# 780-00012-P1_Sch_M2_Focus_Drive_old.net
KiCad netlist of a schematic drawn in Altium Designer
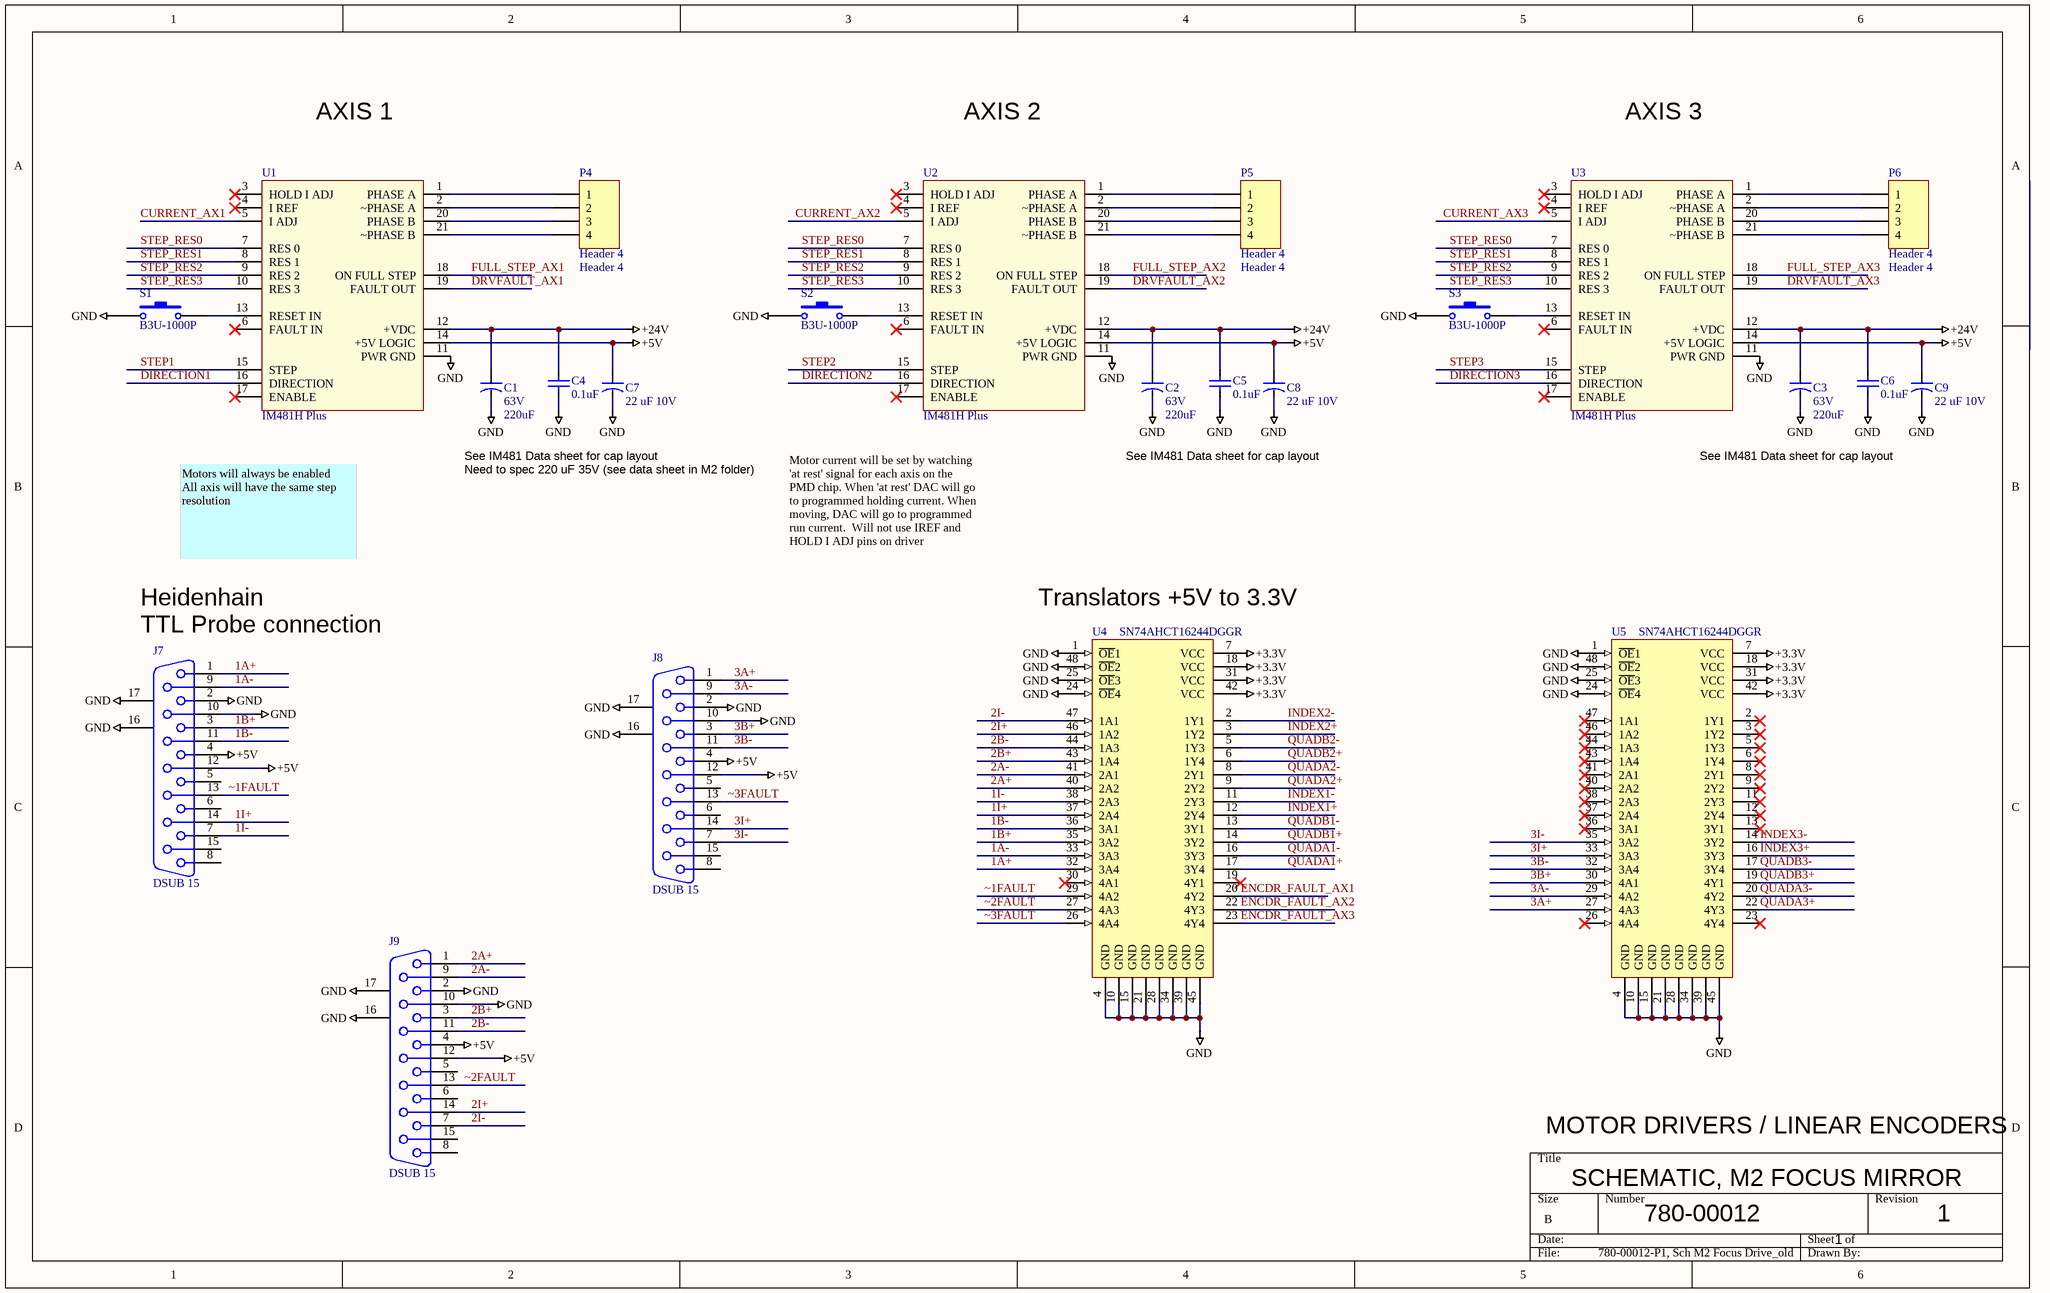
[diagram p0: 780-00012-P1, Sch M2 Focus Drive_old.SchDoc]

(export (version "E")
  (design (tool "Eeschema 10.0.6"))
  (components
    (comp (ref "C1")
      (value "63V")
      (footprint "CAP 220uF 63V")
      (description "CAP 220UF 63V ELECT MVH SMD")
      (fields (field (name "MANUFACTURER") "United Chemi-Con") (field (name "ALTIUM_VALUE") "220uF"))
      (libsource (lib "Richs Schematic Components") (part "Cap 220uF, 63V"))
    )
    (comp (ref "C2")
      (value "63V")
      (footprint "CAP 220uF 63V")
      (description "CAP 220UF 63V ELECT MVH SMD")
      (fields (field (name "MANUFACTURER") "United Chemi-Con") (field (name "ALTIUM_VALUE") "220uF"))
      (libsource (lib "Richs Schematic Components") (part "Cap 220uF, 63V"))
    )
    (comp (ref "C3")
      (value "63V")
      (footprint "CAP 220uF 63V")
      (description "CAP 220UF 63V ELECT MVH SMD")
      (fields (field (name "MANUFACTURER") "United Chemi-Con") (field (name "ALTIUM_VALUE") "220uF"))
      (libsource (lib "Richs Schematic Components") (part "Cap 220uF, 63V"))
    )
    (comp (ref "C4")
      (value "0.1uF")
      (footprint "SMD_0805")
      (description "Capacitor")
      (fields (field (name "Comment") "Cap SMD"))
      (libsource (lib "Richs Schematic Components") (part "Cap SMD"))
    )
    (comp (ref "C5")
      (value "0.1uF")
      (footprint "SMD_0805")
      (description "Capacitor")
      (fields (field (name "Comment") "Cap SMD"))
      (libsource (lib "Richs Schematic Components") (part "Cap SMD"))
    )
    (comp (ref "C6")
      (value "0.1uF")
      (footprint "SMD_0805")
      (description "Capacitor")
      (fields (field (name "Comment") "Cap SMD"))
      (libsource (lib "Richs Schematic Components") (part "Cap SMD"))
    )
    (comp (ref "C7")
      (value "22 uF 10V")
      (footprint "SMD_CAP_3216")
      (description "outline 3.2mm x 1.6mm")
      (fields (field (name "MANUFACTURER") "KEMET") (field (name "Comment") "16V"))
      (libsource (lib "Richs Schematic Components") (part "Cap Tant 16V"))
    )
    (comp (ref "C8")
      (value "22 uF 10V")
      (footprint "SMD_CAP_3216")
      (description "outline 3.2mm x 1.6mm")
      (fields (field (name "MANUFACTURER") "KEMET") (field (name "Comment") "16V"))
      (libsource (lib "Richs Schematic Components") (part "Cap Tant 16V"))
    )
    (comp (ref "C9")
      (value "22 uF 10V")
      (footprint "SMD_CAP_3216")
      (description "outline 3.2mm x 1.6mm")
      (fields (field (name "MANUFACTURER") "KEMET") (field (name "Comment") "16V"))
      (libsource (lib "Richs Schematic Components") (part "Cap Tant 16V"))
    )
    (comp (ref "J7")
      (value "DSUB 15")
      (footprint "DSUB15 PCB VERT Female")
      (description "Receptacle Assembly, 15 Position")
      (fields (field (name "PUBLISHER") "Altium Limited"))
      (libsource (lib "Richs Schematic Components") (part "DSUB 15"))
    )
    (comp (ref "J8")
      (value "DSUB 15")
      (footprint "DSUB15 PCB VERT Female")
      (description "Receptacle Assembly, 15 Position")
      (fields (field (name "PUBLISHER") "Altium Limited"))
      (libsource (lib "Richs Schematic Components") (part "DSUB 15"))
    )
    (comp (ref "J9")
      (value "DSUB 15")
      (footprint "DSUB15 PCB VERT Female")
      (description "Receptacle Assembly, 15 Position")
      (fields (field (name "PUBLISHER") "Altium Limited"))
      (libsource (lib "Richs Schematic Components") (part "DSUB 15"))
    )
    (comp (ref "P4")
      (value "Header 4")
      (footprint "HDR1X4 for IDC")
      (description "Header, 4-Pin")
      (fields (field (name "ALTIUM_VALUE") "Header 4"))
      (libsource (lib "Richs Schematic Components") (part "Header 4"))
    )
    (comp (ref "P5")
      (value "Header 4")
      (footprint "HDR1X4 for IDC")
      (description "Header, 4-Pin")
      (fields (field (name "ALTIUM_VALUE") "Header 4"))
      (libsource (lib "Richs Schematic Components") (part "Header 4"))
    )
    (comp (ref "P6")
      (value "Header 4")
      (footprint "HDR1X4 for IDC")
      (description "Header, 4-Pin")
      (fields (field (name "ALTIUM_VALUE") "Header 4"))
      (libsource (lib "Richs Schematic Components") (part "Header 4"))
    )
    (comp (ref "S1")
      (value "B3U-1000P")
      (footprint "B3U-1000P")
      (description "Switch")
      (fields (field (name "MANUFACTURER") "Omron Electronics"))
      (libsource (lib "Miscellaneous Devices") (part "SW-PB"))
    )
    (comp (ref "S2")
      (value "B3U-1000P")
      (footprint "B3U-1000P")
      (description "Switch")
      (fields (field (name "MANUFACTURER") "Omron Electronics"))
      (libsource (lib "Miscellaneous Devices") (part "SW-PB"))
    )
    (comp (ref "S3")
      (value "B3U-1000P")
      (footprint "B3U-1000P")
      (description "Switch")
      (fields (field (name "MANUFACTURER") "Omron Electronics"))
      (libsource (lib "Miscellaneous Devices") (part "SW-PB"))
    )
    (comp (ref "U1")
      (value "IM481H Plus")
      (footprint "IM481H Vertical")
      (description "Hybrid stepper motor driver")
      (libsource (lib "Richs Schematic Components") (part "IM481H Plus"))
    )
    (comp (ref "U2")
      (value "IM481H Plus")
      (footprint "IM481H Vertical")
      (description "Hybrid stepper motor driver")
      (libsource (lib "Richs Schematic Components") (part "IM481H Plus"))
    )
    (comp (ref "U3")
      (value "IM481H Plus")
      (footprint "IM481H Vertical")
      (description "Hybrid stepper motor driver")
      (libsource (lib "Richs Schematic Components") (part "IM481H Plus"))
    )
    (comp (ref "U4")
      (value "SN74AHCT16244DGGR")
      (footprint "DGG048_N")
      (description "16-Bit Buffer/Driver with 3-State Outputs")
      (fields (field (name "PUBLISHER") "Altium Limited"))
      (libsource (lib "TI Logic Buffer Line Driver") (part "SN74AHCT16244DGGR"))
    )
    (comp (ref "U5")
      (value "SN74AHCT16244DGGR")
      (footprint "DGG048_N")
      (description "16-Bit Buffer/Driver with 3-State Outputs")
      (fields (field (name "PUBLISHER") "Altium Limited"))
      (libsource (lib "TI Logic Buffer Line Driver") (part "SN74AHCT16244DGGR"))
    )
  )
  (nets
    (net (code "1") (name "+3.3V") (class "Default")
      (node (ref "U4") (pin "18") (pinfunction "VCC_18") (pintype "power_in"))
      (node (ref "U4") (pin "31") (pinfunction "VCC_31") (pintype "power_in"))
      (node (ref "U4") (pin "42") (pinfunction "VCC_42") (pintype "power_in"))
      (node (ref "U4") (pin "7") (pinfunction "VCC_7") (pintype "power_in"))
      (node (ref "U5") (pin "18") (pinfunction "VCC_18") (pintype "power_in"))
      (node (ref "U5") (pin "31") (pinfunction "VCC_31") (pintype "power_in"))
      (node (ref "U5") (pin "42") (pinfunction "VCC_42") (pintype "power_in"))
      (node (ref "U5") (pin "7") (pinfunction "VCC_7") (pintype "power_in"))
    )
    (net (code "2") (name "+5V") (class "Default")
      (node (ref "C7") (pin "1") (pinfunction "1_1") (pintype "passive"))
      (node (ref "C8") (pin "1") (pinfunction "1_1") (pintype "passive"))
      (node (ref "C9") (pin "1") (pinfunction "1_1") (pintype "passive"))
      (node (ref "J7") (pin "12") (pinfunction "12_12") (pintype "passive"))
      (node (ref "J7") (pin "4") (pinfunction "4_4") (pintype "passive"))
      (node (ref "J8") (pin "12") (pinfunction "12_12") (pintype "passive"))
      (node (ref "J8") (pin "4") (pinfunction "4_4") (pintype "passive"))
      (node (ref "J9") (pin "12") (pinfunction "12_12") (pintype "passive"))
      (node (ref "J9") (pin "4") (pinfunction "4_4") (pintype "passive"))
      (node (ref "U1") (pin "14") (pinfunction "+5V_LOGIC_14") (pintype "passive"))
      (node (ref "U2") (pin "14") (pinfunction "+5V_LOGIC_14") (pintype "passive"))
      (node (ref "U3") (pin "14") (pinfunction "+5V_LOGIC_14") (pintype "passive"))
    )
    (net (code "3") (name "+24V") (class "Default")
      (node (ref "C1") (pin "1") (pinfunction "1_1") (pintype "passive"))
      (node (ref "C2") (pin "1") (pinfunction "1_1") (pintype "passive"))
      (node (ref "C3") (pin "1") (pinfunction "1_1") (pintype "passive"))
      (node (ref "C4") (pin "2") (pinfunction "2_2") (pintype "passive"))
      (node (ref "C5") (pin "2") (pinfunction "2_2") (pintype "passive"))
      (node (ref "C6") (pin "2") (pinfunction "2_2") (pintype "passive"))
      (node (ref "U1") (pin "12") (pinfunction "+VDC_12") (pintype "passive"))
      (node (ref "U2") (pin "12") (pinfunction "+VDC_12") (pintype "passive"))
      (node (ref "U3") (pin "12") (pinfunction "+VDC_12") (pintype "passive"))
    )
    (net (code "4") (name "/1A+") (class "Default")
      (node (ref "J7") (pin "1") (pinfunction "1_1") (pintype "passive"))
      (node (ref "U4") (pin "32") (pinfunction "3A4_32") (pintype "input"))
    )
    (net (code "5") (name "/1A-") (class "Default")
      (node (ref "J7") (pin "9") (pinfunction "9_9") (pintype "passive"))
      (node (ref "U4") (pin "33") (pinfunction "3A3_33") (pintype "input"))
    )
    (net (code "6") (name "/1B+") (class "Default")
      (node (ref "J7") (pin "3") (pinfunction "3_3") (pintype "passive"))
      (node (ref "U4") (pin "35") (pinfunction "3A2_35") (pintype "input"))
    )
    (net (code "7") (name "/1B-") (class "Default")
      (node (ref "J7") (pin "11") (pinfunction "11_11") (pintype "passive"))
      (node (ref "U4") (pin "36") (pinfunction "3A1_36") (pintype "input"))
    )
    (net (code "8") (name "/1I+") (class "Default")
      (node (ref "J7") (pin "14") (pinfunction "14_14") (pintype "passive"))
      (node (ref "U4") (pin "37") (pinfunction "2A4_37") (pintype "input"))
    )
    (net (code "9") (name "/1I-") (class "Default")
      (node (ref "J7") (pin "7") (pinfunction "7_7") (pintype "passive"))
      (node (ref "U4") (pin "38") (pinfunction "2A3_38") (pintype "input"))
    )
    (net (code "10") (name "/2A+") (class "Default")
      (node (ref "J9") (pin "1") (pinfunction "1_1") (pintype "passive"))
      (node (ref "U4") (pin "40") (pinfunction "2A2_40") (pintype "input"))
    )
    (net (code "11") (name "/2A-") (class "Default")
      (node (ref "J9") (pin "9") (pinfunction "9_9") (pintype "passive"))
      (node (ref "U4") (pin "41") (pinfunction "2A1_41") (pintype "input"))
    )
    (net (code "12") (name "/2B+") (class "Default")
      (node (ref "J9") (pin "3") (pinfunction "3_3") (pintype "passive"))
      (node (ref "U4") (pin "43") (pinfunction "1A4_43") (pintype "input"))
    )
    (net (code "13") (name "/2B-") (class "Default")
      (node (ref "J9") (pin "11") (pinfunction "11_11") (pintype "passive"))
      (node (ref "U4") (pin "44") (pinfunction "1A3_44") (pintype "input"))
    )
    (net (code "14") (name "/2I+") (class "Default")
      (node (ref "J9") (pin "14") (pinfunction "14_14") (pintype "passive"))
      (node (ref "U4") (pin "46") (pinfunction "1A2_46") (pintype "input"))
    )
    (net (code "15") (name "/2I-") (class "Default")
      (node (ref "J9") (pin "7") (pinfunction "7_7") (pintype "passive"))
      (node (ref "U4") (pin "47") (pinfunction "1A1_47") (pintype "input"))
    )
    (net (code "16") (name "/3A+") (class "Default")
      (node (ref "J8") (pin "1") (pinfunction "1_1") (pintype "passive"))
      (node (ref "U5") (pin "27") (pinfunction "4A3_27") (pintype "input"))
    )
    (net (code "17") (name "/3A-") (class "Default")
      (node (ref "J8") (pin "9") (pinfunction "9_9") (pintype "passive"))
      (node (ref "U5") (pin "29") (pinfunction "4A2_29") (pintype "input"))
    )
    (net (code "18") (name "/3B+") (class "Default")
      (node (ref "J8") (pin "3") (pinfunction "3_3") (pintype "passive"))
      (node (ref "U5") (pin "30") (pinfunction "4A1_30") (pintype "input"))
    )
    (net (code "19") (name "/3B-") (class "Default")
      (node (ref "J8") (pin "11") (pinfunction "11_11") (pintype "passive"))
      (node (ref "U5") (pin "32") (pinfunction "3A4_32") (pintype "input"))
    )
    (net (code "20") (name "/3I+") (class "Default")
      (node (ref "J8") (pin "14") (pinfunction "14_14") (pintype "passive"))
      (node (ref "U5") (pin "33") (pinfunction "3A3_33") (pintype "input"))
    )
    (net (code "21") (name "/3I-") (class "Default")
      (node (ref "J8") (pin "7") (pinfunction "7_7") (pintype "passive"))
      (node (ref "U5") (pin "35") (pinfunction "3A2_35") (pintype "input"))
    )
    (net (code "22") (name "/CURRENT_AX1") (class "Default")
      (node (ref "U1") (pin "5") (pinfunction "I_ADJ_5") (pintype "passive"))
    )
    (net (code "23") (name "/CURRENT_AX2") (class "Default")
      (node (ref "U2") (pin "5") (pinfunction "I_ADJ_5") (pintype "passive"))
    )
    (net (code "24") (name "/CURRENT_AX3") (class "Default")
      (node (ref "U3") (pin "5") (pinfunction "I_ADJ_5") (pintype "passive"))
    )
    (net (code "25") (name "/DIRECTION1") (class "Default")
      (node (ref "U1") (pin "16") (pinfunction "DIRECTION_16") (pintype "passive"))
    )
    (net (code "26") (name "/DIRECTION2") (class "Default")
      (node (ref "U2") (pin "16") (pinfunction "DIRECTION_16") (pintype "passive"))
    )
    (net (code "27") (name "/DIRECTION3") (class "Default")
      (node (ref "U3") (pin "16") (pinfunction "DIRECTION_16") (pintype "passive"))
    )
    (net (code "28") (name "/DRVFAULT_AX1") (class "Default")
      (node (ref "U1") (pin "19") (pinfunction "FAULT_OUT_19") (pintype "passive"))
    )
    (net (code "29") (name "/DRVFAULT_AX2") (class "Default")
      (node (ref "U2") (pin "19") (pinfunction "FAULT_OUT_19") (pintype "passive"))
    )
    (net (code "30") (name "/DRVFAULT_AX3") (class "Default")
      (node (ref "U3") (pin "19") (pinfunction "FAULT_OUT_19") (pintype "passive"))
    )
    (net (code "31") (name "/ENCDR_FAULT_AX1") (class "Default")
      (node (ref "U4") (pin "20") (pinfunction "4Y2_20") (pintype "tri_state"))
    )
    (net (code "32") (name "/ENCDR_FAULT_AX2") (class "Default")
      (node (ref "U4") (pin "22") (pinfunction "4Y3_22") (pintype "tri_state"))
    )
    (net (code "33") (name "/ENCDR_FAULT_AX3") (class "Default")
      (node (ref "U4") (pin "23") (pinfunction "4Y4_23") (pintype "tri_state"))
    )
    (net (code "34") (name "/FULL_STEP_AX1") (class "Default")
      (node (ref "U1") (pin "18") (pinfunction "ON_FULL_STEP_18") (pintype "passive"))
    )
    (net (code "35") (name "/FULL_STEP_AX2") (class "Default")
      (node (ref "U2") (pin "18") (pinfunction "ON_FULL_STEP_18") (pintype "passive"))
    )
    (net (code "36") (name "/FULL_STEP_AX3") (class "Default")
      (node (ref "U3") (pin "18") (pinfunction "ON_FULL_STEP_18") (pintype "passive"))
    )
    (net (code "37") (name "/INDEX1+") (class "Default")
      (node (ref "U4") (pin "12") (pinfunction "2Y4_12") (pintype "tri_state"))
    )
    (net (code "38") (name "/INDEX1-") (class "Default")
      (node (ref "U4") (pin "11") (pinfunction "2Y3_11") (pintype "tri_state"))
    )
    (net (code "39") (name "/INDEX2+") (class "Default")
      (node (ref "U4") (pin "3") (pinfunction "1Y2_3") (pintype "tri_state"))
    )
    (net (code "40") (name "/INDEX2-") (class "Default")
      (node (ref "U4") (pin "2") (pinfunction "1Y1_2") (pintype "tri_state"))
    )
    (net (code "41") (name "/INDEX3+") (class "Default")
      (node (ref "U5") (pin "16") (pinfunction "3Y3_16") (pintype "tri_state"))
    )
    (net (code "42") (name "/INDEX3-") (class "Default")
      (node (ref "U5") (pin "14") (pinfunction "3Y2_14") (pintype "tri_state"))
    )
    (net (code "43") (name "/QUADA1+") (class "Default")
      (node (ref "U4") (pin "17") (pinfunction "3Y4_17") (pintype "tri_state"))
    )
    (net (code "44") (name "/QUADA1-") (class "Default")
      (node (ref "U4") (pin "16") (pinfunction "3Y3_16") (pintype "tri_state"))
    )
    (net (code "45") (name "/QUADA2+") (class "Default")
      (node (ref "U4") (pin "9") (pinfunction "2Y2_9") (pintype "tri_state"))
    )
    (net (code "46") (name "/QUADA2-") (class "Default")
      (node (ref "U4") (pin "8") (pinfunction "2Y1_8") (pintype "tri_state"))
    )
    (net (code "47") (name "/QUADA3+") (class "Default")
      (node (ref "U5") (pin "22") (pinfunction "4Y3_22") (pintype "tri_state"))
    )
    (net (code "48") (name "/QUADA3-") (class "Default")
      (node (ref "U5") (pin "20") (pinfunction "4Y2_20") (pintype "tri_state"))
    )
    (net (code "49") (name "/QUADB1+") (class "Default")
      (node (ref "U4") (pin "14") (pinfunction "3Y2_14") (pintype "tri_state"))
    )
    (net (code "50") (name "/QUADB1-") (class "Default")
      (node (ref "U4") (pin "13") (pinfunction "3Y1_13") (pintype "tri_state"))
    )
    (net (code "51") (name "/QUADB2+") (class "Default")
      (node (ref "U4") (pin "6") (pinfunction "1Y4_6") (pintype "tri_state"))
    )
    (net (code "52") (name "/QUADB2-") (class "Default")
      (node (ref "U4") (pin "5") (pinfunction "1Y3_5") (pintype "tri_state"))
    )
    (net (code "53") (name "/QUADB3+") (class "Default")
      (node (ref "U5") (pin "19") (pinfunction "4Y1_19") (pintype "tri_state"))
    )
    (net (code "54") (name "/QUADB3-") (class "Default")
      (node (ref "U5") (pin "17") (pinfunction "3Y4_17") (pintype "tri_state"))
    )
    (net (code "55") (name "/STEP1") (class "Default")
      (node (ref "U1") (pin "15") (pinfunction "STEP_15") (pintype "passive"))
    )
    (net (code "56") (name "/STEP2") (class "Default")
      (node (ref "U2") (pin "15") (pinfunction "STEP_15") (pintype "passive"))
    )
    (net (code "57") (name "/STEP3") (class "Default")
      (node (ref "U3") (pin "15") (pinfunction "STEP_15") (pintype "passive"))
    )
    (net (code "58") (name "/STEP_RES0") (class "Default")
      (node (ref "U1") (pin "7") (pinfunction "RES_0_7") (pintype "passive"))
      (node (ref "U2") (pin "7") (pinfunction "RES_0_7") (pintype "passive"))
      (node (ref "U3") (pin "7") (pinfunction "RES_0_7") (pintype "passive"))
    )
    (net (code "59") (name "/STEP_RES1") (class "Default")
      (node (ref "U1") (pin "8") (pinfunction "RES_1_8") (pintype "passive"))
      (node (ref "U2") (pin "8") (pinfunction "RES_1_8") (pintype "passive"))
      (node (ref "U3") (pin "8") (pinfunction "RES_1_8") (pintype "passive"))
    )
    (net (code "60") (name "/STEP_RES2") (class "Default")
      (node (ref "U1") (pin "9") (pinfunction "RES_2_9") (pintype "passive"))
      (node (ref "U2") (pin "9") (pinfunction "RES_2_9") (pintype "passive"))
      (node (ref "U3") (pin "9") (pinfunction "RES_2_9") (pintype "passive"))
    )
    (net (code "61") (name "/STEP_RES3") (class "Default")
      (node (ref "U1") (pin "10") (pinfunction "RES_3_10") (pintype "passive"))
      (node (ref "U2") (pin "10") (pinfunction "RES_3_10") (pintype "passive"))
      (node (ref "U3") (pin "10") (pinfunction "RES_3_10") (pintype "passive"))
    )
    (net (code "62") (name "/~1FAULT") (class "Default")
      (node (ref "J7") (pin "13") (pinfunction "13_13") (pintype "passive"))
      (node (ref "U4") (pin "29") (pinfunction "4A2_29") (pintype "input"))
    )
    (net (code "63") (name "/~2FAULT") (class "Default")
      (node (ref "J9") (pin "13") (pinfunction "13_13") (pintype "passive"))
      (node (ref "U4") (pin "27") (pinfunction "4A3_27") (pintype "input"))
    )
    (net (code "64") (name "/~3FAULT") (class "Default")
      (node (ref "J8") (pin "13") (pinfunction "13_13") (pintype "passive"))
      (node (ref "U4") (pin "26") (pinfunction "4A4_26") (pintype "input"))
    )
    (net (code "65") (name "GND") (class "Default")
      (node (ref "C1") (pin "2") (pinfunction "2_2") (pintype "passive"))
      (node (ref "C2") (pin "2") (pinfunction "2_2") (pintype "passive"))
      (node (ref "C3") (pin "2") (pinfunction "2_2") (pintype "passive"))
      (node (ref "C4") (pin "1") (pinfunction "1_1") (pintype "passive"))
      (node (ref "C5") (pin "1") (pinfunction "1_1") (pintype "passive"))
      (node (ref "C6") (pin "1") (pinfunction "1_1") (pintype "passive"))
      (node (ref "C7") (pin "2") (pinfunction "2_2") (pintype "passive"))
      (node (ref "C8") (pin "2") (pinfunction "2_2") (pintype "passive"))
      (node (ref "C9") (pin "2") (pinfunction "2_2") (pintype "passive"))
      (node (ref "J7") (pin "10") (pinfunction "10_10") (pintype "passive"))
      (node (ref "J7") (pin "16") (pinfunction "MH1_16") (pintype "passive"))
      (node (ref "J7") (pin "17") (pinfunction "MH2_17") (pintype "passive"))
      (node (ref "J7") (pin "2") (pinfunction "2_2") (pintype "passive"))
      (node (ref "J8") (pin "10") (pinfunction "10_10") (pintype "passive"))
      (node (ref "J8") (pin "16") (pinfunction "MH1_16") (pintype "passive"))
      (node (ref "J8") (pin "17") (pinfunction "MH2_17") (pintype "passive"))
      (node (ref "J8") (pin "2") (pinfunction "2_2") (pintype "passive"))
      (node (ref "J9") (pin "10") (pinfunction "10_10") (pintype "passive"))
      (node (ref "J9") (pin "16") (pinfunction "MH1_16") (pintype "passive"))
      (node (ref "J9") (pin "17") (pinfunction "MH2_17") (pintype "passive"))
      (node (ref "J9") (pin "2") (pinfunction "2_2") (pintype "passive"))
      (node (ref "S1") (pin "1") (pinfunction "1_1") (pintype "passive"))
      (node (ref "S2") (pin "1") (pinfunction "1_1") (pintype "passive"))
      (node (ref "S3") (pin "1") (pinfunction "1_1") (pintype "passive"))
      (node (ref "U1") (pin "11") (pinfunction "PWR_GND_11") (pintype "passive"))
      (node (ref "U2") (pin "11") (pinfunction "PWR_GND_11") (pintype "passive"))
      (node (ref "U3") (pin "11") (pinfunction "PWR_GND_11") (pintype "passive"))
      (node (ref "U4") (pin "1") (pinfunction "~{OE}1_1") (pintype "input"))
      (node (ref "U4") (pin "10") (pinfunction "GND_10") (pintype "power_in"))
      (node (ref "U4") (pin "15") (pinfunction "GND_15") (pintype "power_in"))
      (node (ref "U4") (pin "21") (pinfunction "GND_21") (pintype "power_in"))
      (node (ref "U4") (pin "24") (pinfunction "~{OE}4_24") (pintype "input"))
      (node (ref "U4") (pin "25") (pinfunction "~{OE}3_25") (pintype "input"))
      (node (ref "U4") (pin "28") (pinfunction "GND_28") (pintype "power_in"))
      (node (ref "U4") (pin "34") (pinfunction "GND_34") (pintype "power_in"))
      (node (ref "U4") (pin "39") (pinfunction "GND_39") (pintype "power_in"))
      (node (ref "U4") (pin "4") (pinfunction "GND_4") (pintype "power_in"))
      (node (ref "U4") (pin "45") (pinfunction "GND_45") (pintype "power_in"))
      (node (ref "U4") (pin "48") (pinfunction "~{OE}2_48") (pintype "input"))
      (node (ref "U5") (pin "1") (pinfunction "~{OE}1_1") (pintype "input"))
      (node (ref "U5") (pin "10") (pinfunction "GND_10") (pintype "power_in"))
      (node (ref "U5") (pin "15") (pinfunction "GND_15") (pintype "power_in"))
      (node (ref "U5") (pin "21") (pinfunction "GND_21") (pintype "power_in"))
      (node (ref "U5") (pin "24") (pinfunction "~{OE}4_24") (pintype "input"))
      (node (ref "U5") (pin "25") (pinfunction "~{OE}3_25") (pintype "input"))
      (node (ref "U5") (pin "28") (pinfunction "GND_28") (pintype "power_in"))
      (node (ref "U5") (pin "34") (pinfunction "GND_34") (pintype "power_in"))
      (node (ref "U5") (pin "39") (pinfunction "GND_39") (pintype "power_in"))
      (node (ref "U5") (pin "4") (pinfunction "GND_4") (pintype "power_in"))
      (node (ref "U5") (pin "45") (pinfunction "GND_45") (pintype "power_in"))
      (node (ref "U5") (pin "48") (pinfunction "~{OE}2_48") (pintype "input"))
    )
    (net (code "66") (name "Net-(U1-PHASE_A)") (class "Default")
      (node (ref "P4") (pin "1") (pinfunction "1_1") (pintype "passive"))
      (node (ref "U1") (pin "1") (pinfunction "PHASE_A_1") (pintype "passive"))
    )
    (net (code "67") (name "Net-(U1-PHASE_B)") (class "Default")
      (node (ref "P4") (pin "3") (pinfunction "3_3") (pintype "passive"))
      (node (ref "U1") (pin "20") (pinfunction "PHASE_B_20") (pintype "passive"))
    )
    (net (code "68") (name "Net-(U1-RESET_IN)") (class "Default")
      (node (ref "S1") (pin "2") (pinfunction "2_2") (pintype "passive"))
      (node (ref "U1") (pin "13") (pinfunction "RESET_IN_13") (pintype "passive"))
    )
    (net (code "69") (name "Net-(U1-~PHASE_A)") (class "Default")
      (node (ref "P4") (pin "2") (pinfunction "2_2") (pintype "passive"))
      (node (ref "U1") (pin "2") (pinfunction "~PHASE_A_2") (pintype "passive"))
    )
    (net (code "70") (name "Net-(U1-~PHASE_B)") (class "Default")
      (node (ref "P4") (pin "4") (pinfunction "4_4") (pintype "passive"))
      (node (ref "U1") (pin "21") (pinfunction "~PHASE_B_21") (pintype "passive"))
    )
    (net (code "71") (name "Net-(U2-PHASE_A)") (class "Default")
      (node (ref "P5") (pin "1") (pinfunction "1_1") (pintype "passive"))
      (node (ref "U2") (pin "1") (pinfunction "PHASE_A_1") (pintype "passive"))
    )
    (net (code "72") (name "Net-(U2-PHASE_B)") (class "Default")
      (node (ref "P5") (pin "3") (pinfunction "3_3") (pintype "passive"))
      (node (ref "U2") (pin "20") (pinfunction "PHASE_B_20") (pintype "passive"))
    )
    (net (code "73") (name "Net-(U2-RESET_IN)") (class "Default")
      (node (ref "S2") (pin "2") (pinfunction "2_2") (pintype "passive"))
      (node (ref "U2") (pin "13") (pinfunction "RESET_IN_13") (pintype "passive"))
    )
    (net (code "74") (name "Net-(U2-~PHASE_A)") (class "Default")
      (node (ref "P5") (pin "2") (pinfunction "2_2") (pintype "passive"))
      (node (ref "U2") (pin "2") (pinfunction "~PHASE_A_2") (pintype "passive"))
    )
    (net (code "75") (name "Net-(U2-~PHASE_B)") (class "Default")
      (node (ref "P5") (pin "4") (pinfunction "4_4") (pintype "passive"))
      (node (ref "U2") (pin "21") (pinfunction "~PHASE_B_21") (pintype "passive"))
    )
    (net (code "76") (name "Net-(U3-PHASE_A)") (class "Default")
      (node (ref "P6") (pin "1") (pinfunction "1_1") (pintype "passive"))
      (node (ref "U3") (pin "1") (pinfunction "PHASE_A_1") (pintype "passive"))
    )
    (net (code "77") (name "Net-(U3-PHASE_B)") (class "Default")
      (node (ref "P6") (pin "3") (pinfunction "3_3") (pintype "passive"))
      (node (ref "U3") (pin "20") (pinfunction "PHASE_B_20") (pintype "passive"))
    )
    (net (code "78") (name "Net-(U3-RESET_IN)") (class "Default")
      (node (ref "S3") (pin "2") (pinfunction "2_2") (pintype "passive"))
      (node (ref "U3") (pin "13") (pinfunction "RESET_IN_13") (pintype "passive"))
    )
    (net (code "79") (name "Net-(U3-~PHASE_A)") (class "Default")
      (node (ref "P6") (pin "2") (pinfunction "2_2") (pintype "passive"))
      (node (ref "U3") (pin "2") (pinfunction "~PHASE_A_2") (pintype "passive"))
    )
    (net (code "80") (name "Net-(U3-~PHASE_B)") (class "Default")
      (node (ref "P6") (pin "4") (pinfunction "4_4") (pintype "passive"))
      (node (ref "U3") (pin "21") (pinfunction "~PHASE_B_21") (pintype "passive"))
    )
    (net (code "81") (name "unconnected-(J7-Pad5)") (class "Default")
      (node (ref "J7") (pin "5") (pinfunction "5_5") (pintype "passive"))
    )
    (net (code "82") (name "unconnected-(J7-Pad6)") (class "Default")
      (node (ref "J7") (pin "6") (pinfunction "6_6") (pintype "passive"))
    )
    (net (code "83") (name "unconnected-(J7-Pad8)") (class "Default")
      (node (ref "J7") (pin "8") (pinfunction "8_8") (pintype "passive"))
    )
    (net (code "84") (name "unconnected-(J7-Pad15)") (class "Default")
      (node (ref "J7") (pin "15") (pinfunction "15_15") (pintype "passive"))
    )
    (net (code "85") (name "unconnected-(J8-Pad5)") (class "Default")
      (node (ref "J8") (pin "5") (pinfunction "5_5") (pintype "passive"))
    )
    (net (code "86") (name "unconnected-(J8-Pad6)") (class "Default")
      (node (ref "J8") (pin "6") (pinfunction "6_6") (pintype "passive"))
    )
    (net (code "87") (name "unconnected-(J8-Pad8)") (class "Default")
      (node (ref "J8") (pin "8") (pinfunction "8_8") (pintype "passive"))
    )
    (net (code "88") (name "unconnected-(J8-Pad15)") (class "Default")
      (node (ref "J8") (pin "15") (pinfunction "15_15") (pintype "passive"))
    )
    (net (code "89") (name "unconnected-(J9-Pad5)") (class "Default")
      (node (ref "J9") (pin "5") (pinfunction "5_5") (pintype "passive"))
    )
    (net (code "90") (name "unconnected-(J9-Pad6)") (class "Default")
      (node (ref "J9") (pin "6") (pinfunction "6_6") (pintype "passive"))
    )
    (net (code "91") (name "unconnected-(J9-Pad8)") (class "Default")
      (node (ref "J9") (pin "8") (pinfunction "8_8") (pintype "passive"))
    )
    (net (code "92") (name "unconnected-(J9-Pad15)") (class "Default")
      (node (ref "J9") (pin "15") (pinfunction "15_15") (pintype "passive"))
    )
    (net (code "93") (name "unconnected-(U1-ENABLE-Pad17)") (class "Default")
      (node (ref "U1") (pin "17") (pinfunction "ENABLE_17") (pintype "passive+no_connect"))
    )
    (net (code "94") (name "unconnected-(U1-FAULT_IN-Pad6)") (class "Default")
      (node (ref "U1") (pin "6") (pinfunction "FAULT_IN_6") (pintype "passive+no_connect"))
    )
    (net (code "95") (name "unconnected-(U1-HOLD_I_ADJ-Pad3)") (class "Default")
      (node (ref "U1") (pin "3") (pinfunction "HOLD_I_ADJ_3") (pintype "passive+no_connect"))
    )
    (net (code "96") (name "unconnected-(U1-I_REF-Pad4)") (class "Default")
      (node (ref "U1") (pin "4") (pinfunction "I_REF_4") (pintype "passive+no_connect"))
    )
    (net (code "97") (name "unconnected-(U2-ENABLE-Pad17)") (class "Default")
      (node (ref "U2") (pin "17") (pinfunction "ENABLE_17") (pintype "passive+no_connect"))
    )
    (net (code "98") (name "unconnected-(U2-FAULT_IN-Pad6)") (class "Default")
      (node (ref "U2") (pin "6") (pinfunction "FAULT_IN_6") (pintype "passive+no_connect"))
    )
    (net (code "99") (name "unconnected-(U2-HOLD_I_ADJ-Pad3)") (class "Default")
      (node (ref "U2") (pin "3") (pinfunction "HOLD_I_ADJ_3") (pintype "passive+no_connect"))
    )
    (net (code "100") (name "unconnected-(U2-I_REF-Pad4)") (class "Default")
      (node (ref "U2") (pin "4") (pinfunction "I_REF_4") (pintype "passive+no_connect"))
    )
    (net (code "101") (name "unconnected-(U3-ENABLE-Pad17)") (class "Default")
      (node (ref "U3") (pin "17") (pinfunction "ENABLE_17") (pintype "passive+no_connect"))
    )
    (net (code "102") (name "unconnected-(U3-FAULT_IN-Pad6)") (class "Default")
      (node (ref "U3") (pin "6") (pinfunction "FAULT_IN_6") (pintype "passive+no_connect"))
    )
    (net (code "103") (name "unconnected-(U3-HOLD_I_ADJ-Pad3)") (class "Default")
      (node (ref "U3") (pin "3") (pinfunction "HOLD_I_ADJ_3") (pintype "passive+no_connect"))
    )
    (net (code "104") (name "unconnected-(U3-I_REF-Pad4)") (class "Default")
      (node (ref "U3") (pin "4") (pinfunction "I_REF_4") (pintype "passive+no_connect"))
    )
    (net (code "105") (name "unconnected-(U4-4A1-Pad30)") (class "Default")
      (node (ref "U4") (pin "30") (pinfunction "4A1_30") (pintype "input+no_connect"))
    )
    (net (code "106") (name "unconnected-(U4-4Y1-Pad19)") (class "Default")
      (node (ref "U4") (pin "19") (pinfunction "4Y1_19") (pintype "tri_state+no_connect"))
    )
    (net (code "107") (name "unconnected-(U5-1A1-Pad47)") (class "Default")
      (node (ref "U5") (pin "47") (pinfunction "1A1_47") (pintype "input+no_connect"))
    )
    (net (code "108") (name "unconnected-(U5-1A2-Pad46)") (class "Default")
      (node (ref "U5") (pin "46") (pinfunction "1A2_46") (pintype "input+no_connect"))
    )
    (net (code "109") (name "unconnected-(U5-1A3-Pad44)") (class "Default")
      (node (ref "U5") (pin "44") (pinfunction "1A3_44") (pintype "input+no_connect"))
    )
    (net (code "110") (name "unconnected-(U5-1A4-Pad43)") (class "Default")
      (node (ref "U5") (pin "43") (pinfunction "1A4_43") (pintype "input+no_connect"))
    )
    (net (code "111") (name "unconnected-(U5-1Y1-Pad2)") (class "Default")
      (node (ref "U5") (pin "2") (pinfunction "1Y1_2") (pintype "tri_state+no_connect"))
    )
    (net (code "112") (name "unconnected-(U5-1Y2-Pad3)") (class "Default")
      (node (ref "U5") (pin "3") (pinfunction "1Y2_3") (pintype "tri_state+no_connect"))
    )
    (net (code "113") (name "unconnected-(U5-1Y3-Pad5)") (class "Default")
      (node (ref "U5") (pin "5") (pinfunction "1Y3_5") (pintype "tri_state+no_connect"))
    )
    (net (code "114") (name "unconnected-(U5-1Y4-Pad6)") (class "Default")
      (node (ref "U5") (pin "6") (pinfunction "1Y4_6") (pintype "tri_state+no_connect"))
    )
    (net (code "115") (name "unconnected-(U5-2A1-Pad41)") (class "Default")
      (node (ref "U5") (pin "41") (pinfunction "2A1_41") (pintype "input+no_connect"))
    )
    (net (code "116") (name "unconnected-(U5-2A2-Pad40)") (class "Default")
      (node (ref "U5") (pin "40") (pinfunction "2A2_40") (pintype "input+no_connect"))
    )
    (net (code "117") (name "unconnected-(U5-2A3-Pad38)") (class "Default")
      (node (ref "U5") (pin "38") (pinfunction "2A3_38") (pintype "input+no_connect"))
    )
    (net (code "118") (name "unconnected-(U5-2A4-Pad37)") (class "Default")
      (node (ref "U5") (pin "37") (pinfunction "2A4_37") (pintype "input+no_connect"))
    )
    (net (code "119") (name "unconnected-(U5-2Y1-Pad8)") (class "Default")
      (node (ref "U5") (pin "8") (pinfunction "2Y1_8") (pintype "tri_state+no_connect"))
    )
    (net (code "120") (name "unconnected-(U5-2Y2-Pad9)") (class "Default")
      (node (ref "U5") (pin "9") (pinfunction "2Y2_9") (pintype "tri_state+no_connect"))
    )
    (net (code "121") (name "unconnected-(U5-2Y3-Pad11)") (class "Default")
      (node (ref "U5") (pin "11") (pinfunction "2Y3_11") (pintype "tri_state+no_connect"))
    )
    (net (code "122") (name "unconnected-(U5-2Y4-Pad12)") (class "Default")
      (node (ref "U5") (pin "12") (pinfunction "2Y4_12") (pintype "tri_state+no_connect"))
    )
    (net (code "123") (name "unconnected-(U5-3A1-Pad36)") (class "Default")
      (node (ref "U5") (pin "36") (pinfunction "3A1_36") (pintype "input+no_connect"))
    )
    (net (code "124") (name "unconnected-(U5-3Y1-Pad13)") (class "Default")
      (node (ref "U5") (pin "13") (pinfunction "3Y1_13") (pintype "tri_state+no_connect"))
    )
    (net (code "125") (name "unconnected-(U5-4A4-Pad26)") (class "Default")
      (node (ref "U5") (pin "26") (pinfunction "4A4_26") (pintype "input+no_connect"))
    )
    (net (code "126") (name "unconnected-(U5-4Y4-Pad23)") (class "Default")
      (node (ref "U5") (pin "23") (pinfunction "4Y4_23") (pintype "tri_state+no_connect"))
    )
  )
)
